# SuperCap-NEW_V2_0.net
KiCad netlist of a schematic drawn in Altium Designer
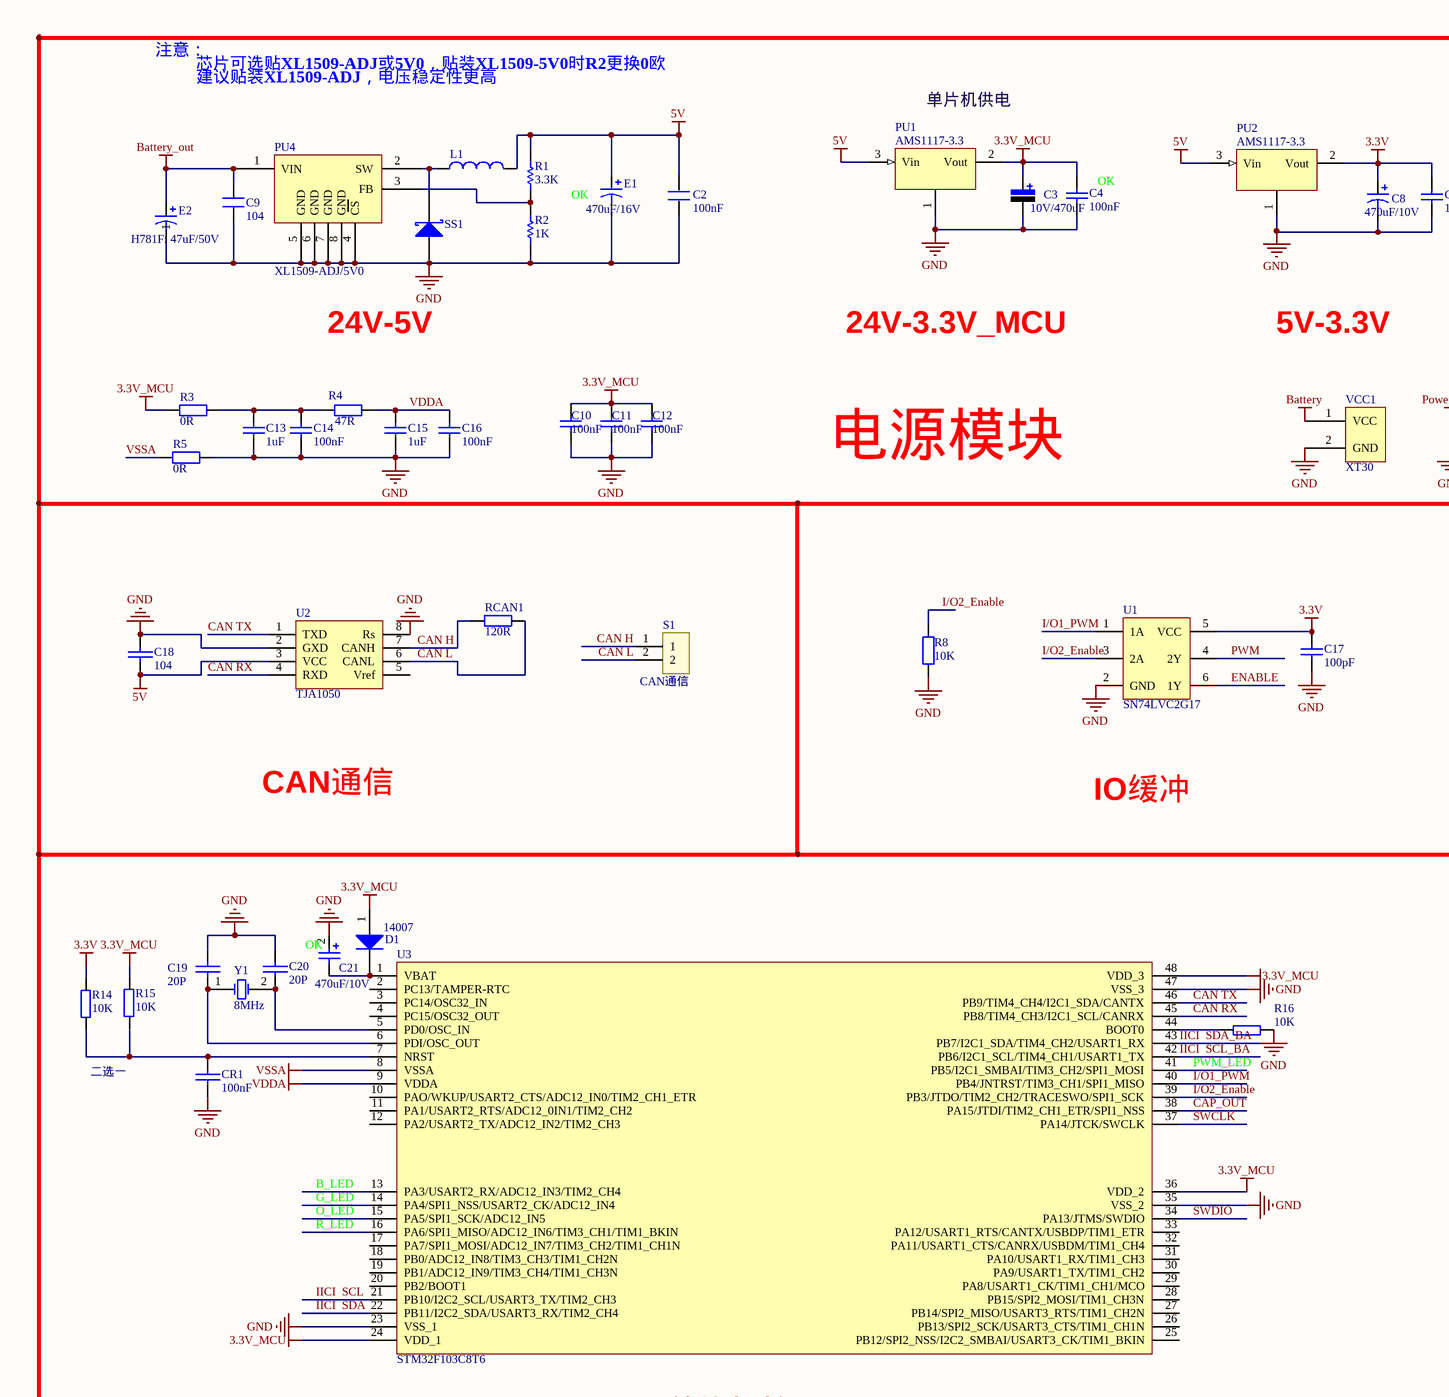
[diagram p0: SuperCap-NEW_V2.0.SchDoc, top left]
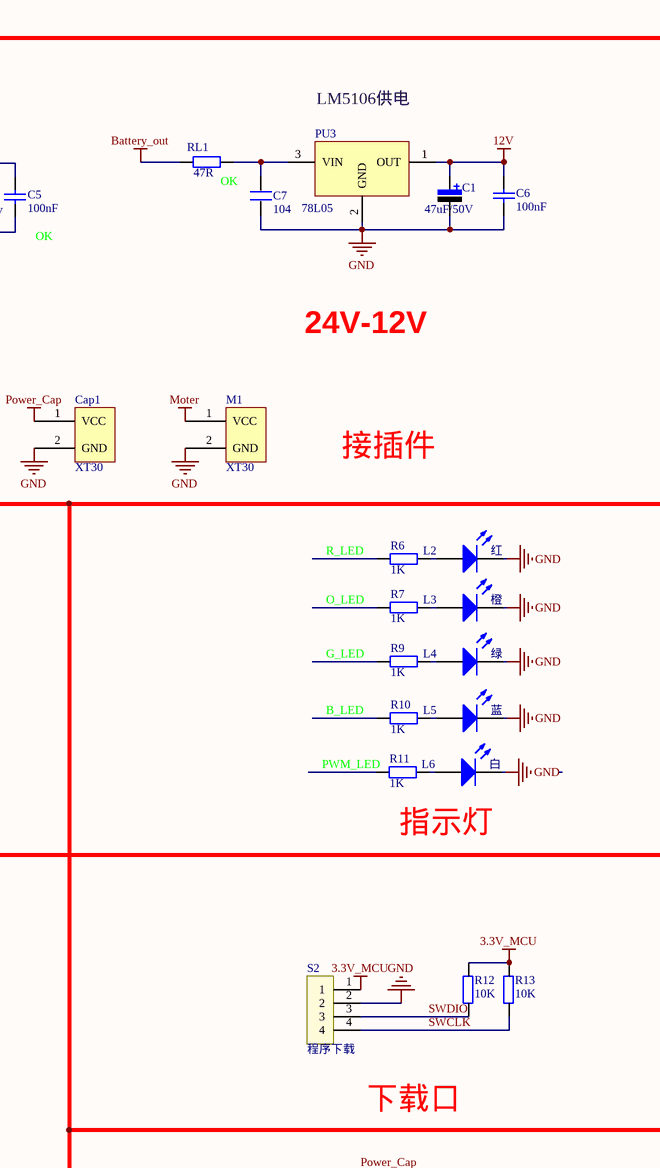
[diagram p1: SuperCap-NEW_V2.0.SchDoc, top right]
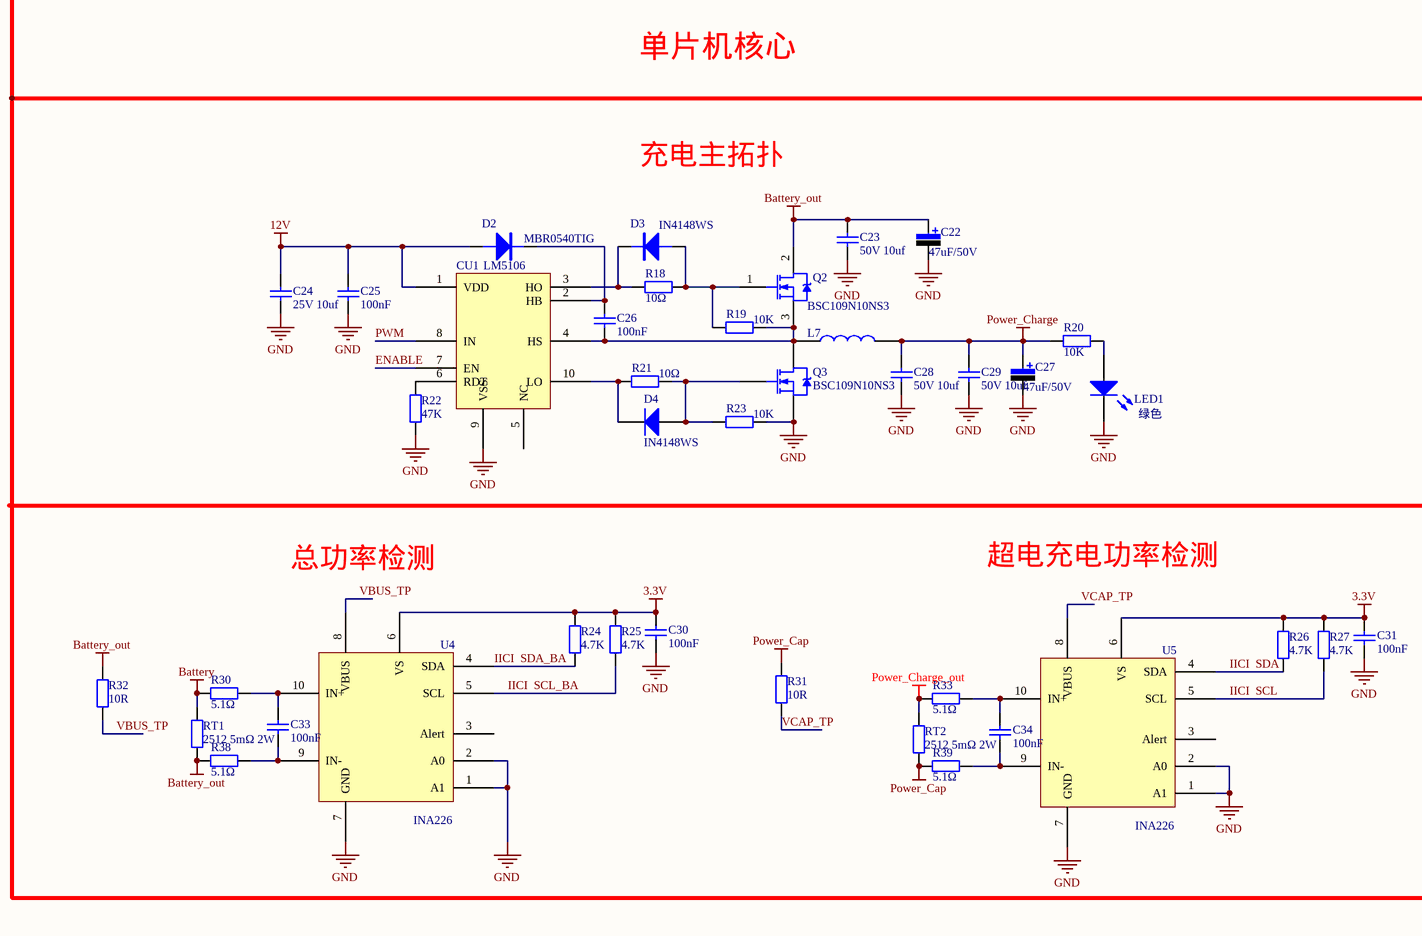
[diagram p2: SuperCap-NEW_V2.0.SchDoc, bottom left]
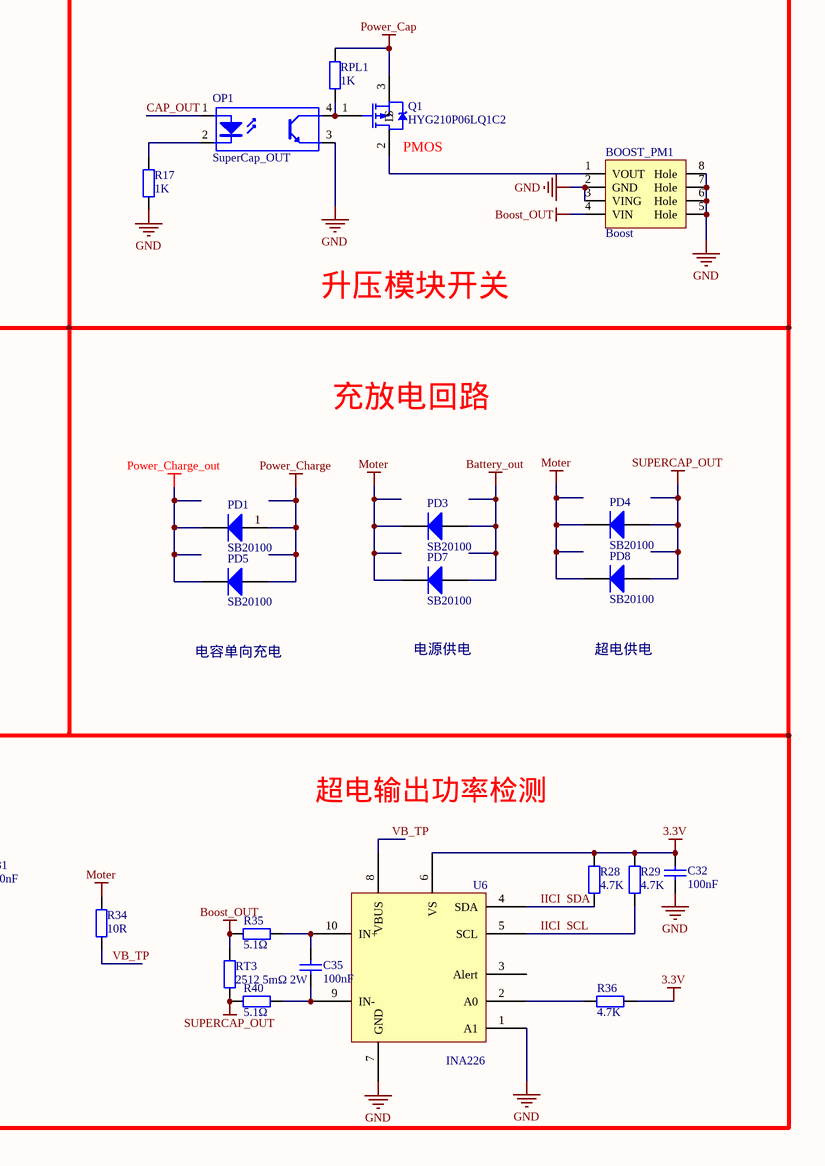
[diagram p3: SuperCap-NEW_V2.0.SchDoc, bottom right]

(export (version "E")
  (design (tool "Eeschema 10.0.6"))
  (components
    (comp (ref "BOOST_PM1")
      (value "Boost")
      (footprint "Boost_Block")
      (libsource (lib "My package") (part "Boost"))
    )
    (comp (ref "C1")
      (value "47uF/50V")
      (footprint "CAP-SMD_BD6.3-L6.6-W6.6-FD")
      (description "极性电解电容")
      (fields (field (name "PUBLISHER") "Altium Limited"))
      (libsource (lib "Fszhang") (part "Cap Pol"))
    )
    (comp (ref "C2") (value "100nF") (footprint "0603C") (libsource (lib "南江主控 原理图库") (part "C")))
    (comp (ref "C3")
      (value "10V/470uF")
      (footprint "CAP-SMD_BD6.3-L6.6-W6.6-FD")
      (description "极性电解电容")
      (fields (field (name "PUBLISHER") "Altium Limited"))
      (libsource (lib "Fszhang") (part "Cap Pol"))
    )
    (comp (ref "C4")
      (value "100nF")
      (footprint "0603C")
      (description "无极性电容")
      (fields (field (name "PUBLISHER") "Altium Limited"))
      (libsource (lib "Fszhang") (part "Cap"))
    )
    (comp (ref "C5")
      (value "100nF")
      (footprint "0603C")
      (description "无极性电容")
      (fields (field (name "PUBLISHER") "Altium Limited"))
      (libsource (lib "Fszhang") (part "Cap"))
    )
    (comp (ref "C6")
      (value "100nF")
      (footprint "0603C")
      (description "无极性电容")
      (fields (field (name "PUBLISHER") "Altium Limited"))
      (libsource (lib "Fszhang") (part "Cap"))
    )
    (comp (ref "C7") (value "104") (footprint "0603C") (libsource (lib "103驱动2") (part "C")))
    (comp (ref "C8")
      (value "470uF/10V")
      (footprint "CAP-SMD_BD6.3-L6.6-W6.6-FD")
      (description "Polarized Capacitor (Radial)")
      (fields (field (name "Comment") "Cap Pol1") (field (name "PUBLISHER") "Altium Limited"))
      (libsource (lib "") (part "Cap Pol1_1"))
    )
    (comp (ref "C9") (value "104") (footprint "0603C") (libsource (lib "南江主控 原理图库") (part "C")))
    (comp (ref "C10")
      (value "100nF")
      (footprint "0603C")
      (description "无极性电容")
      (fields (field (name "PUBLISHER") "Altium Limited"))
      (libsource (lib "Fszhang") (part "Cap"))
    )
    (comp (ref "C11")
      (value "100nF")
      (footprint "0603C")
      (description "无极性电容")
      (fields (field (name "PUBLISHER") "Altium Limited"))
      (libsource (lib "Fszhang") (part "Cap"))
    )
    (comp (ref "C12")
      (value "100nF")
      (footprint "0603C")
      (description "无极性电容")
      (fields (field (name "PUBLISHER") "Altium Limited"))
      (libsource (lib "Fszhang") (part "Cap"))
    )
    (comp (ref "C13")
      (value "1uF")
      (footprint "0603C")
      (description "无极性电容")
      (fields (field (name "PUBLISHER") "Altium Limited"))
      (libsource (lib "Fszhang") (part "Cap"))
    )
    (comp (ref "C14")
      (value "100nF")
      (footprint "0603C")
      (description "无极性电容")
      (fields (field (name "PUBLISHER") "Altium Limited"))
      (libsource (lib "Fszhang") (part "Cap"))
    )
    (comp (ref "C15")
      (value "1uF")
      (footprint "0603C")
      (description "无极性电容")
      (fields (field (name "PUBLISHER") "Altium Limited"))
      (libsource (lib "Fszhang") (part "Cap"))
    )
    (comp (ref "C16")
      (value "100nF")
      (footprint "0603C")
      (description "无极性电容")
      (fields (field (name "PUBLISHER") "Altium Limited"))
      (libsource (lib "Fszhang") (part "Cap"))
    )
    (comp (ref "C17")
      (value "100pF")
      (footprint "0603C")
      (description "Capacitor")
      (fields (field (name "Comment") "Cap") (field (name "PUBLISHER") "Altium Limited"))
      (libsource (lib "Miscellaneous Devices") (part "Cap"))
    )
    (comp (ref "C18") (value "104") (footprint "0603C") (libsource (lib "ZBC124Schlib1") (part "CAP-1")))
    (comp (ref "C19") (value "20P") (footprint "0603C") (libsource (lib "ZBC124Schlib1") (part "CAP-1")))
    (comp (ref "C20") (value "20P") (footprint "0603C") (libsource (lib "ZBC124Schlib1") (part "CAP-1")))
    (comp (ref "C21")
      (value "470uF/10V")
      (footprint "CAP-SMD_BD6.3-L6.6-W6.6-FD")
      (description "Polarized Capacitor (Radial)")
      (fields (field (name "PUBLISHER") "Altium Limited"))
      (libsource (lib "*") (part "Cap Pol1"))
    )
    (comp (ref "C22")
      (value "47uF/50V")
      (footprint "CAP-SMD_BD6.3-L6.6-W6.6-FD")
      (description "极性电解电容")
      (fields (field (name "PUBLISHER") "Altium Limited"))
      (libsource (lib "Fszhang") (part "Cap Pol"))
    )
    (comp (ref "C23")
      (value "50V 10uf")
      (footprint "0603C")
      (description "无极性电容")
      (fields (field (name "PUBLISHER") "Altium Limited"))
      (libsource (lib "Fszhang") (part "Cap"))
    )
    (comp (ref "C24")
      (value "25V 10uf")
      (footprint "0603C")
      (description "无极性电容")
      (fields (field (name "PUBLISHER") "Altium Limited"))
      (libsource (lib "Fszhang") (part "Cap"))
    )
    (comp (ref "C25")
      (value "100nF")
      (footprint "0603C")
      (description "无极性电容")
      (fields (field (name "PUBLISHER") "Altium Limited"))
      (libsource (lib "Fszhang") (part "Cap"))
    )
    (comp (ref "C26")
      (value "100nF")
      (footprint "0603C")
      (description "无极性电容")
      (fields (field (name "PUBLISHER") "Altium Limited"))
      (libsource (lib "Fszhang") (part "Cap"))
    )
    (comp (ref "C27")
      (value "47uF/50V")
      (footprint "CAP-SMD_BD6.3-L6.6-W6.6-FD")
      (description "极性电解电容")
      (fields (field (name "PUBLISHER") "Altium Limited"))
      (libsource (lib "Fszhang") (part "Cap Pol"))
    )
    (comp (ref "C28")
      (value "50V 10uf")
      (footprint "0603C")
      (description "无极性电容")
      (fields (field (name "PUBLISHER") "Altium Limited"))
      (libsource (lib "Fszhang") (part "Cap"))
    )
    (comp (ref "C29")
      (value "50V 10uf")
      (footprint "0603C")
      (description "无极性电容")
      (fields (field (name "PUBLISHER") "Altium Limited"))
      (libsource (lib "Fszhang") (part "Cap"))
    )
    (comp (ref "C30")
      (value "100nF")
      (footprint "0603C")
      (description "无极性电容")
      (fields (field (name "PUBLISHER") "Altium Limited"))
      (libsource (lib "Fszhang") (part "Cap"))
    )
    (comp (ref "C31")
      (value "100nF")
      (footprint "0603C")
      (description "无极性电容")
      (fields (field (name "PUBLISHER") "Altium Limited"))
      (libsource (lib "Fszhang") (part "Cap"))
    )
    (comp (ref "C32")
      (value "100nF")
      (footprint "0603C")
      (description "无极性电容")
      (fields (field (name "PUBLISHER") "Altium Limited"))
      (libsource (lib "Fszhang") (part "Cap"))
    )
    (comp (ref "C33")
      (value "100nF")
      (footprint "0603C")
      (description "无极性电容")
      (fields (field (name "PUBLISHER") "Altium Limited"))
      (libsource (lib "Fszhang") (part "Cap"))
    )
    (comp (ref "C34")
      (value "100nF")
      (footprint "0603C")
      (description "无极性电容")
      (fields (field (name "PUBLISHER") "Altium Limited"))
      (libsource (lib "Fszhang") (part "Cap"))
    )
    (comp (ref "C35")
      (value "100nF")
      (footprint "0603C")
      (description "无极性电容")
      (fields (field (name "PUBLISHER") "Altium Limited"))
      (libsource (lib "Fszhang") (part "Cap"))
    )
    (comp (ref "Cap1") (value "XT30") (footprint "XT30") (libsource (lib "电源模块") (part "JP-2")))
    (comp (ref "CR1") (value "100nF") (footprint "0603C") (libsource (lib "ZBC124Schlib1") (part "CAP-1")))
    (comp (ref "CU1") (value "LM5106") (footprint "MSOP_10") (libsource (lib "Schlib3") (part "Component_1")))
    (comp (ref "D1")
      (value "14007")
      (footprint "SOD123")
      (description "High Conductance Fast Diode")
      (fields (field (name "PUBLISHER") "Altium Limited"))
      (libsource (lib "") (part "Diode 1N914_1"))
    )
    (comp (ref "D2") (value "MBR0540TIG") (footprint "SOD123") (libsource (lib "ZBC124Schlib1") (part "D-1")))
    (comp (ref "D3") (value "IN4148WS") (footprint "SOD123") (libsource (lib "ZBC124Schlib1") (part "D-1")))
    (comp (ref "D4")
      (value "IN4148WS")
      (footprint "SOD123")
      (description "High Conductance Fast Diode")
      (fields (field (name "PUBLISHER") "Altium Limited"))
      (libsource (lib "Miscellaneous Devices") (part "Diode 1N914"))
    )
    (comp (ref "E1")
      (value "470uF/16V")
      (footprint "CAP-SMD_BD8.0-L8.3-W8.3-FD")
      (description "Polarized Capacitor (Radial)")
      (fields (field (name "Comment") "Cap Pol1") (field (name "PUBLISHER") "Altium Limited"))
      (libsource (lib "") (part "Cap Pol1_1"))
    )
    (comp (ref "E2")
      (value "Cap Pol1")
      (footprint "CAP-SMD_BD8.0-L8.3-W8.3-FD")
      (description "Polarized Capacitor (Radial)")
      (fields (field (name "H781F") "47uF/50V") (field (name "PUBLISHER") "Altium Limited"))
      (libsource (lib "Miscellaneous Devices") (part "Cap Pol1"))
    )
    (comp (ref "L1")
      (value "Inductor")
      (footprint "L 6*6")
      (fields (field (name "PUBLISHER") "Altium Limited"))
      (libsource (lib "Miscellaneous Devices") (part "Inductor"))
    )
    (comp (ref "L2")
      (value "红")
      (footprint "LED_0805")
      (description "发光二极管")
      (fields (field (name "PUBLISHER") "Altium Limited"))
      (libsource (lib "Fszhang") (part "LED0"))
    )
    (comp (ref "L3")
      (value "橙")
      (footprint "LED_0805")
      (description "发光二极管")
      (fields (field (name "PUBLISHER") "Altium Limited"))
      (libsource (lib "Fszhang") (part "LED0"))
    )
    (comp (ref "L4")
      (value "绿")
      (footprint "LED_0805")
      (description "发光二极管")
      (fields (field (name "PUBLISHER") "Altium Limited"))
      (libsource (lib "Fszhang") (part "LED0"))
    )
    (comp (ref "L5")
      (value "蓝")
      (footprint "LED_0805")
      (description "发光二极管")
      (fields (field (name "PUBLISHER") "Altium Limited"))
      (libsource (lib "Fszhang") (part "LED0"))
    )
    (comp (ref "L6")
      (value "白")
      (footprint "LED_0805")
      (description "发光二极管")
      (fields (field (name "PUBLISHER") "Altium Limited"))
      (libsource (lib "Fszhang") (part "LED0"))
    )
    (comp (ref "L7")
      (value "68UH")
      (footprint "IND-TH_L14.0-W6.5-P8.00-D0.6")
      (libsource (lib "103驱动2") (part "Inductance"))
    )
    (comp (ref "LED1")
      (value "绿色")
      (footprint "LED_0805")
      (description "发光二极管")
      (fields (field (name "PUBLISHER") "Altium Limited"))
      (libsource (lib "Fszhang") (part "LED0"))
    )
    (comp (ref "M1") (value "XT30") (footprint "XT30") (libsource (lib "电源模块") (part "JP-2")))
    (comp (ref "OP1")
      (value "SuperCap_OUT")
      (footprint "SOP-4_L6.5-W4.6-P2.54-LS10.2-TL")
      (description "4-Pin Phototransistor Optocoupler")
      (fields (field (name "PUBLISHER") "Altium Limited"))
      (libsource (lib "Miscellaneous Devices") (part "Optoisolator1"))
    )
    (comp (ref "PD1")
      (value "SB20100")
      (footprint "TO-277_3P-L5.4-W4.0-LS6.5-TR")
      (description "High Conductance Fast Diode")
      (fields (field (name "PUBLISHER") "Altium Limited"))
      (libsource (lib "") (part "Diode 1N914_1"))
    )
    (comp (ref "PD3")
      (value "SB20100")
      (footprint "TO-277_3P-L5.4-W4.0-LS6.5-TR")
      (description "High Conductance Fast Diode")
      (fields (field (name "PUBLISHER") "Altium Limited"))
      (libsource (lib "Miscellaneous Devices") (part "Diode 1N914"))
    )
    (comp (ref "PD4")
      (value "SB20100")
      (footprint "TO-277_3P-L5.4-W4.0-LS6.5-TR")
      (description "High Conductance Fast Diode")
      (fields (field (name "PUBLISHER") "Altium Limited"))
      (libsource (lib "Miscellaneous Devices") (part "Diode 1N914"))
    )
    (comp (ref "PD5")
      (value "SB20100")
      (footprint "TO-277_3P-L5.4-W4.0-LS6.5-TR")
      (description "High Conductance Fast Diode")
      (fields (field (name "PUBLISHER") "Altium Limited"))
      (libsource (lib "Miscellaneous Devices") (part "Diode 1N914"))
    )
    (comp (ref "PD7")
      (value "SB20100")
      (footprint "TO-277_3P-L5.4-W4.0-LS6.5-TR")
      (description "High Conductance Fast Diode")
      (fields (field (name "PUBLISHER") "Altium Limited"))
      (libsource (lib "Miscellaneous Devices") (part "Diode 1N914"))
    )
    (comp (ref "PD8")
      (value "SB20100")
      (footprint "TO-277_3P-L5.4-W4.0-LS6.5-TR")
      (description "High Conductance Fast Diode")
      (fields (field (name "PUBLISHER") "Altium Limited"))
      (libsource (lib "Miscellaneous Devices") (part "Diode 1N914"))
    )
    (comp (ref "PU1") (value "AMS1117-3.3") (footprint "SOT-223") (libsource (lib "*") (part "LD1117")))
    (comp (ref "PU2") (value "AMS1117-3.3") (footprint "SOT-223") (libsource (lib "*") (part "LD1117")))
    (comp (ref "PU3")
      (value "78L05")
      (footprint "SOT-89-3_L4.5-W2.5-P1.50-LS4.2-BR")
      (libsource (lib "My package") (part "78L05"))
    )
    (comp (ref "PU4")
      (value "XL1509-ADJ/5V0")
      (footprint "SOP8 N")
      (libsource (lib "电源转接板") (part "XL1509-ADJ"))
    )
    (comp (ref "Q1")
      (value "HYG210P06LQ1C2")
      (footprint "MOS_PQFN")
      (description "P-Channel Power MOSFET")
      (fields (field (name "PUBLISHER") "Altium Limited"))
      (libsource (lib "Miscellaneous Devices") (part "PMOS-2"))
    )
    (comp (ref "Q2")
      (value "BSC109N10NS3")
      (footprint "PDFN-8_L4.9-W5.8-P1.27-LS6.1-BL_2")
      (description "N-Channel Power MOSFET")
      (fields (field (name "PUBLISHER") "Altium Limited"))
      (libsource (lib "Miscellaneous Devices") (part "NMOS-2"))
    )
    (comp (ref "Q3")
      (value "BSC109N10NS3")
      (footprint "PDFN-8_L4.9-W5.8-P1.27-LS6.1-BL_2")
      (description "N-Channel Power MOSFET")
      (fields (field (name "PUBLISHER") "Altium Limited"))
      (libsource (lib "") (part "NMOS-2_1"))
    )
    (comp (ref "R1")
      (value "3.3K")
      (footprint "R0603")
      (description "Resistor")
      (fields (field (name "Comment") "Res1") (field (name "PUBLISHER") "Altium Limited"))
      (libsource (lib "Miscellaneous Devices") (part "Res1"))
    )
    (comp (ref "R2")
      (value "1K")
      (footprint "R0603")
      (description "Resistor")
      (fields (field (name "Comment") "Res1") (field (name "PUBLISHER") "Altium Limited"))
      (libsource (lib "Miscellaneous Devices") (part "Res1"))
    )
    (comp (ref "R3")
      (value "0R")
      (footprint "0603-1")
      (description "贴片电阻")
      (fields (field (name "PUBLISHER") "Altium Limited"))
      (libsource (lib "") (part "Res1_2"))
    )
    (comp (ref "R4")
      (value "47R")
      (footprint "0603-1")
      (description "贴片电阻")
      (fields (field (name "PUBLISHER") "Altium Limited"))
      (libsource (lib "") (part "Res1_2"))
    )
    (comp (ref "R5")
      (value "0R")
      (footprint "0603-1")
      (description "贴片电阻")
      (fields (field (name "PUBLISHER") "Altium Limited"))
      (libsource (lib "") (part "Res1_2"))
    )
    (comp (ref "R6")
      (value "1K")
      (footprint "0603-1")
      (description "Resistor")
      (fields (field (name "Comment") "Res2") (field (name "PUBLISHER") "Altium Limited"))
      (libsource (lib "") (part "Res2_1"))
    )
    (comp (ref "R7")
      (value "1K")
      (footprint "0603-1")
      (description "Resistor")
      (fields (field (name "Comment") "Res2") (field (name "PUBLISHER") "Altium Limited"))
      (libsource (lib "Miscellaneous Devices") (part "Res2"))
    )
    (comp (ref "R8")
      (value "10K")
      (footprint "0603-1")
      (description "Resistor")
      (fields (field (name "Comment") "Res2") (field (name "PUBLISHER") "Altium Limited"))
      (libsource (lib "") (part "Res2_2"))
    )
    (comp (ref "R9")
      (value "1K")
      (footprint "0603-1")
      (description "Resistor")
      (fields (field (name "Comment") "Res2") (field (name "PUBLISHER") "Altium Limited"))
      (libsource (lib "Miscellaneous Devices") (part "Res2"))
    )
    (comp (ref "R10")
      (value "1K")
      (footprint "0603-1")
      (description "Resistor")
      (fields (field (name "Comment") "Res2") (field (name "PUBLISHER") "Altium Limited"))
      (libsource (lib "Miscellaneous Devices") (part "Res2"))
    )
    (comp (ref "R11")
      (value "1K")
      (footprint "0603-1")
      (description "Resistor")
      (fields (field (name "Comment") "Res2") (field (name "PUBLISHER") "Altium Limited"))
      (libsource (lib "Miscellaneous Devices") (part "Res2"))
    )
    (comp (ref "R12") (value "10K") (footprint "0603-1") (libsource (lib "WARSHIP") (part "R")))
    (comp (ref "R13") (value "10K") (footprint "0603-1") (libsource (lib "WARSHIP") (part "R")))
    (comp (ref "R14") (value "10K") (footprint "0603-1") (libsource (lib "WARSHIP") (part "R")))
    (comp (ref "R15") (value "10K") (footprint "0603-1") (libsource (lib "WARSHIP") (part "R")))
    (comp (ref "R16") (value "10K") (footprint "0603-1") (libsource (lib "WARSHIP") (part "R")))
    (comp (ref "R17")
      (value "1K")
      (footprint "0603-1")
      (description "贴片电阻")
      (fields (field (name "PUBLISHER") "Altium Limited"))
      (libsource (lib "Fszhang") (part "Res1"))
    )
    (comp (ref "R18")
      (value "10Ω")
      (footprint "0603-1")
      (description "贴片电阻")
      (fields (field (name "PUBLISHER") "Altium Limited"))
      (libsource (lib "") (part "Res1_2"))
    )
    (comp (ref "R19")
      (value "10K")
      (footprint "0603-1")
      (description "贴片电阻")
      (fields (field (name "PUBLISHER") "Altium Limited"))
      (libsource (lib "") (part "Res1_2"))
    )
    (comp (ref "R20")
      (value "10K")
      (footprint "0603-1")
      (description "贴片电阻")
      (fields (field (name "PUBLISHER") "Altium Limited"))
      (libsource (lib "") (part "Res1_1"))
    )
    (comp (ref "R21")
      (value "10Ω")
      (footprint "0603-1")
      (description "贴片电阻")
      (fields (field (name "PUBLISHER") "Altium Limited"))
      (libsource (lib "") (part "Res1_2"))
    )
    (comp (ref "R22")
      (value "47K")
      (footprint "0603-1")
      (description "贴片电阻")
      (fields (field (name "PUBLISHER") "Altium Limited"))
      (libsource (lib "Fszhang") (part "Res1"))
    )
    (comp (ref "R23")
      (value "10K")
      (footprint "0603-1")
      (description "贴片电阻")
      (fields (field (name "PUBLISHER") "Altium Limited"))
      (libsource (lib "") (part "Res1_2"))
    )
    (comp (ref "R24")
      (value "4.7K")
      (footprint "0603-1")
      (description "贴片电阻")
      (fields (field (name "PUBLISHER") "Altium Limited"))
      (libsource (lib "Fszhang") (part "Res1"))
    )
    (comp (ref "R25")
      (value "4.7K")
      (footprint "0603-1")
      (description "贴片电阻")
      (fields (field (name "PUBLISHER") "Altium Limited"))
      (libsource (lib "Fszhang") (part "Res1"))
    )
    (comp (ref "R26")
      (value "4.7K")
      (footprint "0603-1")
      (description "贴片电阻")
      (fields (field (name "PUBLISHER") "Altium Limited"))
      (libsource (lib "Fszhang") (part "Res1"))
    )
    (comp (ref "R27")
      (value "4.7K")
      (footprint "0603-1")
      (description "贴片电阻")
      (fields (field (name "PUBLISHER") "Altium Limited"))
      (libsource (lib "Fszhang") (part "Res1"))
    )
    (comp (ref "R28")
      (value "4.7K")
      (footprint "0603-1")
      (description "贴片电阻")
      (fields (field (name "PUBLISHER") "Altium Limited"))
      (libsource (lib "Fszhang") (part "Res1"))
    )
    (comp (ref "R29")
      (value "4.7K")
      (footprint "0603-1")
      (description "贴片电阻")
      (fields (field (name "PUBLISHER") "Altium Limited"))
      (libsource (lib "Fszhang") (part "Res1"))
    )
    (comp (ref "R30")
      (value "5.1Ω")
      (footprint "0603-1")
      (description "贴片电阻")
      (fields (field (name "PUBLISHER") "Altium Limited"))
      (libsource (lib "") (part "Res1_1"))
    )
    (comp (ref "R31")
      (value "10R")
      (footprint "0603-1")
      (description "Resistor")
      (fields (field (name "Comment") "Res2") (field (name "PUBLISHER") "Altium Limited"))
      (libsource (lib "") (part "Res2_2"))
    )
    (comp (ref "R32")
      (value "10R")
      (footprint "0603-1")
      (description "Resistor")
      (fields (field (name "Comment") "Res2") (field (name "PUBLISHER") "Altium Limited"))
      (libsource (lib "") (part "Res2_2"))
    )
    (comp (ref "R33")
      (value "5.1Ω")
      (footprint "0603-1")
      (description "贴片电阻")
      (fields (field (name "PUBLISHER") "Altium Limited"))
      (libsource (lib "") (part "Res1_1"))
    )
    (comp (ref "R34")
      (value "10R")
      (footprint "0603-1")
      (description "Resistor")
      (fields (field (name "Comment") "Res2") (field (name "PUBLISHER") "Altium Limited"))
      (libsource (lib "") (part "Res2_2"))
    )
    (comp (ref "R35")
      (value "5.1Ω")
      (footprint "0603-1")
      (description "贴片电阻")
      (fields (field (name "PUBLISHER") "Altium Limited"))
      (libsource (lib "") (part "Res1_1"))
    )
    (comp (ref "R36")
      (value "4.7K")
      (footprint "0603-1")
      (description "Resistor")
      (fields (field (name "Comment") "Res2") (field (name "PUBLISHER") "Altium Limited"))
      (libsource (lib "") (part "Res2_1"))
    )
    (comp (ref "R38")
      (value "5.1Ω")
      (footprint "0603-1")
      (description "贴片电阻")
      (fields (field (name "PUBLISHER") "Altium Limited"))
      (libsource (lib "") (part "Res1_1"))
    )
    (comp (ref "R39")
      (value "5.1Ω")
      (footprint "0603-1")
      (description "贴片电阻")
      (fields (field (name "PUBLISHER") "Altium Limited"))
      (libsource (lib "") (part "Res1_1"))
    )
    (comp (ref "R40")
      (value "5.1Ω")
      (footprint "0603-1")
      (description "贴片电阻")
      (fields (field (name "PUBLISHER") "Altium Limited"))
      (libsource (lib "") (part "Res1_1"))
    )
    (comp (ref "RCAN1")
      (value "120R")
      (footprint "0603-1")
      (description "Resistor")
      (fields (field (name "Comment") "Res2") (field (name "PUBLISHER") "Altium Limited"))
      (libsource (lib "") (part "Res2_1"))
    )
    (comp (ref "RL1")
      (value "47R")
      (footprint "0603-1")
      (description "贴片电阻")
      (fields (field (name "PUBLISHER") "Altium Limited"))
      (libsource (lib "") (part "Res1_2"))
    )
    (comp (ref "RPL1")
      (value "1K")
      (footprint "0603-1")
      (description "贴片电阻")
      (fields (field (name "PUBLISHER") "Altium Limited"))
      (libsource (lib "Fszhang") (part "Res1"))
    )
    (comp (ref "RT1")
      (value "2512 5mΩ 2W")
      (footprint "FUSE-SMD_L6.1-W2.7 - duplicate")
      (description "贴片电阻")
      (fields (field (name "PUBLISHER") "Altium Limited"))
      (libsource (lib "Fszhang") (part "Res1"))
    )
    (comp (ref "RT2")
      (value "2512 5mΩ 2W")
      (footprint "FUSE-SMD_L6.1-W2.7 - duplicate")
      (description "贴片电阻")
      (fields (field (name "PUBLISHER") "Altium Limited"))
      (libsource (lib "Fszhang") (part "Res1"))
    )
    (comp (ref "RT3")
      (value "2512 5mΩ 2W")
      (footprint "FUSE-SMD_L6.1-W2.7 - duplicate")
      (description "贴片电阻")
      (fields (field (name "PUBLISHER") "Altium Limited"))
      (libsource (lib "Fszhang") (part "Res1"))
    )
    (comp (ref "S1") (value "CAN通信") (footprint "1.25_2Pin") (libsource (lib "ZBC123Schlib1") (part "S-2")))
    (comp (ref "S2") (value "程序下载") (footprint "S-4") (libsource (lib "ZBC123Schlib1") (part "S-4")))
    (comp (ref "SS1")
      (value "D Schottky")
      (footprint "贴片M7")
      (description "Schottky Diode")
      (fields (field (name "PUBLISHER") "Altium Limited"))
      (libsource (lib "Miscellaneous Devices") (part "D Schottky"))
    )
    (comp (ref "U1")
      (value "SN74LVC2G17")
      (footprint "SC-70-6_L2.0-W1.3-P0.65-LS2.1-BL")
      (libsource (lib "My package") (part "SN74LVC2G17"))
    )
    (comp (ref "U2") (value "TJA1050") (footprint "SOP8 N") (libsource (lib "底盘主控") (part "24C02")))
    (comp (ref "U3")
      (value "STM32F103C8T6")
      (footprint "LQFP-48_M")
      (libsource (lib "WARSHIP") (part "STM32F103C8T6"))
    )
    (comp (ref "U4") (value "INA226") (footprint "MSOP_10") (libsource (lib "Schlib4") (part "Component_1")))
    (comp (ref "U5") (value "INA226") (footprint "MSOP_10") (libsource (lib "Schlib4") (part "Component_1")))
    (comp (ref "U6") (value "INA226") (footprint "MSOP_10") (libsource (lib "Schlib4") (part "Component_1")))
    (comp (ref "VCC1") (value "XT30") (footprint "XT30") (libsource (lib "电源模块") (part "JP-2")))
    (comp (ref "Y1")
      (value "8MHz")
      (footprint "X-SM49")
      (description "Crystal Oscillator")
      (fields (field (name "PUBLISHER") "Altium Limited"))
      (libsource (lib "WARSHIP") (part "XTAL"))
    )
  )
  (nets
    (net (code "2") (name "/B_LED") (class "Default")
      (node (ref "R10") (pin "2") (pinfunction "2_2") (pintype "passive"))
      (node (ref "U3") (pin "13") (pinfunction "PA3/USART2_RX/ADC12_IN3/TIM2_CH4_13") (pintype "passive"))
    )
    (net (code "3") (name "/CAN H") (class "Default")
      (node (ref "RCAN1") (pin "1") (pinfunction "1_1") (pintype "passive"))
      (node (ref "S1") (pin "1") (pinfunction "1_1") (pintype "passive"))
      (node (ref "U2") (pin "7") (pinfunction "CANH_7") (pintype "passive"))
    )
    (net (code "4") (name "/CAN L") (class "Default")
      (node (ref "RCAN1") (pin "2") (pinfunction "2_2") (pintype "passive"))
      (node (ref "S1") (pin "2") (pinfunction "2_2") (pintype "passive"))
      (node (ref "U2") (pin "6") (pinfunction "CANL_6") (pintype "passive"))
    )
    (net (code "5") (name "/CAN RX") (class "Default")
      (node (ref "U2") (pin "4") (pinfunction "RXD_4") (pintype "passive"))
      (node (ref "U3") (pin "45") (pinfunction "PB8/TIM4_CH3/I2C1_SCL/CANRX_45") (pintype "passive"))
    )
    (net (code "6") (name "/CAN TX") (class "Default")
      (node (ref "U2") (pin "1") (pinfunction "TXD_1") (pintype "passive"))
      (node (ref "U3") (pin "46") (pinfunction "PB9/TIM4_CH4/I2C1_SDA/CANTX_46") (pintype "passive"))
    )
    (net (code "7") (name "/CAP_OUT") (class "Default")
      (node (ref "OP1") (pin "1") (pinfunction "A_1") (pintype "passive"))
      (node (ref "U3") (pin "38") (pinfunction "PA15/JTDI/TIM2_CH1_ETR/SPI1_NSS_38") (pintype "passive"))
    )
    (net (code "8") (name "/ENABLE") (class "Default")
      (node (ref "CU1") (pin "7") (pinfunction "EN_7") (pintype "passive"))
      (node (ref "U1") (pin "6") (pinfunction "1Y_6") (pintype "passive"))
    )
    (net (code "9") (name "/G_LED") (class "Default")
      (node (ref "R9") (pin "2") (pinfunction "2_2") (pintype "passive"))
      (node (ref "U3") (pin "14") (pinfunction "PA4/SPI1_NSS/USART2_CK/ADC12_IN4_14") (pintype "passive"))
    )
    (net (code "10") (name "/IICI  SCL") (class "Default")
      (node (ref "R27") (pin "2") (pinfunction "2_2") (pintype "passive"))
      (node (ref "R29") (pin "2") (pinfunction "2_2") (pintype "passive"))
      (node (ref "U3") (pin "21") (pinfunction "PB10/I2C2_SCL/USART3_TX/TIM2_CH3_21") (pintype "passive"))
      (node (ref "U5") (pin "5") (pinfunction "SCL_5") (pintype "passive"))
      (node (ref "U6") (pin "5") (pinfunction "SCL_5") (pintype "passive"))
    )
    (net (code "11") (name "/IICI  SCL_BA") (class "Default")
      (node (ref "R25") (pin "2") (pinfunction "2_2") (pintype "passive"))
      (node (ref "U3") (pin "42") (pinfunction "PB6/I2C1_SCL/TIM4_CH1/USART1_TX_42") (pintype "passive"))
      (node (ref "U4") (pin "5") (pinfunction "SCL_5") (pintype "passive"))
    )
    (net (code "12") (name "/IICI  SDA") (class "Default")
      (node (ref "R26") (pin "2") (pinfunction "2_2") (pintype "passive"))
      (node (ref "R28") (pin "2") (pinfunction "2_2") (pintype "passive"))
      (node (ref "U3") (pin "22") (pinfunction "PB11/I2C2_SDA/USART3_RX/TIM2_CH4_22") (pintype "passive"))
      (node (ref "U5") (pin "4") (pinfunction "SDA_4") (pintype "passive"))
      (node (ref "U6") (pin "4") (pinfunction "SDA_4") (pintype "passive"))
    )
    (net (code "13") (name "/IICI  SDA_BA") (class "Default")
      (node (ref "R24") (pin "2") (pinfunction "2_2") (pintype "passive"))
      (node (ref "U3") (pin "43") (pinfunction "PB7/I2C1_SDA/TIM4_CH2/USART1_RX_43") (pintype "passive"))
      (node (ref "U4") (pin "4") (pinfunction "SDA_4") (pintype "passive"))
    )
    (net (code "14") (name "/I{slash}O1_PWM") (class "Default")
      (node (ref "U1") (pin "1") (pinfunction "1A_1") (pintype "passive"))
      (node (ref "U3") (pin "40") (pinfunction "PB4/JNTRST/TIM3_CH1/SPI1_MISO_40") (pintype "passive"))
    )
    (net (code "15") (name "/I{slash}O2_Enable") (class "Default")
      (node (ref "R8") (pin "1") (pinfunction "1_1") (pintype "passive"))
      (node (ref "U1") (pin "3") (pinfunction "2A_3") (pintype "passive"))
      (node (ref "U3") (pin "39") (pinfunction "PB3/JTDO/TIM2_CH2/TRACESWO/SPI1_SCK_39") (pintype "passive"))
    )
    (net (code "17") (name "/O_LED") (class "Default")
      (node (ref "R7") (pin "2") (pinfunction "2_2") (pintype "passive"))
      (node (ref "U3") (pin "15") (pinfunction "PA5/SPI1_SCK/ADC12_IN5_15") (pintype "passive"))
    )
    (net (code "18") (name "/PWM") (class "Default")
      (node (ref "CU1") (pin "8") (pinfunction "IN_8") (pintype "passive"))
      (node (ref "U1") (pin "4") (pinfunction "2Y_4") (pintype "passive"))
    )
    (net (code "19") (name "/PWM_LED") (class "Default")
      (node (ref "R11") (pin "2") (pinfunction "2_2") (pintype "passive"))
      (node (ref "U3") (pin "41") (pinfunction "PB5/I2C1_SMBAI/TIM3_CH2/SPI1_MOSI_41") (pintype "passive"))
    )
    (net (code "20") (name "/R_LED") (class "Default")
      (node (ref "R6") (pin "1") (pinfunction "1_1") (pintype "passive"))
      (node (ref "U3") (pin "16") (pinfunction "PA6/SPI1_MISO/ADC12_IN6/TIM3_CH1/TIM1_BKIN_16") (pintype "passive"))
    )
    (net (code "21") (name "/SWCLK") (class "Default")
      (node (ref "R13") (pin "2") (pintype "passive"))
      (node (ref "S2") (pin "4") (pinfunction "4_4") (pintype "passive"))
      (node (ref "U3") (pin "37") (pinfunction "PA14/JTCK/SWCLK_37") (pintype "passive"))
    )
    (net (code "22") (name "/SWDIO") (class "Default")
      (node (ref "R12") (pin "2") (pintype "passive"))
      (node (ref "S2") (pin "3") (pinfunction "3_3") (pintype "passive"))
      (node (ref "U3") (pin "34") (pinfunction "PA13/JTMS/SWDIO_34") (pintype "passive"))
    )
    (net (code "23") (name "/VBUS_TP") (class "Default")
      (node (ref "R32") (pin "2") (pinfunction "2_2") (pintype "passive"))
      (node (ref "U4") (pin "8") (pinfunction "VBUS_8") (pintype "passive"))
    )
    (net (code "24") (name "/VB_TP") (class "Default")
      (node (ref "R34") (pin "2") (pinfunction "2_2") (pintype "passive"))
      (node (ref "U6") (pin "8") (pinfunction "VBUS_8") (pintype "passive"))
    )
    (net (code "25") (name "/VCAP_TP") (class "Default")
      (node (ref "R31") (pin "2") (pinfunction "2_2") (pintype "passive"))
      (node (ref "U5") (pin "8") (pinfunction "VBUS_8") (pintype "passive"))
    )
    (net (code "27") (name "3.3V") (class "Default")
      (node (ref "C17") (pin "2") (pinfunction "2_2") (pintype "passive"))
      (node (ref "C30") (pin "1") (pinfunction "1_1") (pintype "passive"))
      (node (ref "C31") (pin "1") (pinfunction "1_1") (pintype "passive"))
      (node (ref "C32") (pin "1") (pinfunction "1_1") (pintype "passive"))
      (node (ref "C5") (pin "1") (pinfunction "1_1") (pintype "passive"))
      (node (ref "C8") (pin "1") (pinfunction "1_1") (pintype "passive"))
      (node (ref "PU2") (pin "2") (pinfunction "Vout_2") (pintype "power_in"))
      (node (ref "R14") (pin "1") (pintype "passive"))
      (node (ref "R24") (pin "1") (pinfunction "1_1") (pintype "passive"))
      (node (ref "R25") (pin "1") (pinfunction "1_1") (pintype "passive"))
      (node (ref "R26") (pin "1") (pinfunction "1_1") (pintype "passive"))
      (node (ref "R27") (pin "1") (pinfunction "1_1") (pintype "passive"))
      (node (ref "R28") (pin "1") (pinfunction "1_1") (pintype "passive"))
      (node (ref "R29") (pin "1") (pinfunction "1_1") (pintype "passive"))
      (node (ref "R36") (pin "2") (pinfunction "2_2") (pintype "passive"))
      (node (ref "U1") (pin "5") (pinfunction "VCC_5") (pintype "passive"))
      (node (ref "U4") (pin "6") (pinfunction "VS_6") (pintype "passive"))
      (node (ref "U5") (pin "6") (pinfunction "VS_6") (pintype "passive"))
      (node (ref "U6") (pin "6") (pinfunction "VS_6") (pintype "passive"))
    )
    (net (code "28") (name "3.3V_MCU") (class "Default")
      (node (ref "C10") (pin "1") (pinfunction "1_1") (pintype "passive"))
      (node (ref "C11") (pin "1") (pinfunction "1_1") (pintype "passive"))
      (node (ref "C12") (pin "1") (pinfunction "1_1") (pintype "passive"))
      (node (ref "C3") (pin "1") (pinfunction "1_1") (pintype "passive"))
      (node (ref "C4") (pin "1") (pinfunction "1_1") (pintype "passive"))
      (node (ref "D1") (pin "1") (pinfunction "A_1") (pintype "passive"))
      (node (ref "PU1") (pin "2") (pinfunction "Vout_2") (pintype "power_in"))
      (node (ref "R12") (pin "1") (pintype "passive"))
      (node (ref "R13") (pin "1") (pintype "passive"))
      (node (ref "R15") (pin "1") (pintype "passive"))
      (node (ref "R3") (pin "1") (pinfunction "1_1") (pintype "passive"))
      (node (ref "S2") (pin "1") (pinfunction "1_1") (pintype "passive"))
      (node (ref "U3") (pin "24") (pinfunction "VDD_1_24") (pintype "passive"))
      (node (ref "U3") (pin "36") (pinfunction "VDD_2_36") (pintype "passive"))
      (node (ref "U3") (pin "48") (pinfunction "VDD_3_48") (pintype "passive"))
    )
    (net (code "29") (name "5V") (class "Default")
      (node (ref "C18") (pin "2") (pinfunction "2_2") (pintype "passive"))
      (node (ref "C2") (pin "2") (pintype "passive"))
      (node (ref "E1") (pin "1") (pinfunction "1_1") (pintype "passive"))
      (node (ref "L1") (pin "2") (pinfunction "2_2") (pintype "passive"))
      (node (ref "PU1") (pin "3") (pinfunction "Vin_3") (pintype "input"))
      (node (ref "PU2") (pin "3") (pinfunction "Vin_3") (pintype "input"))
      (node (ref "R1") (pin "2") (pinfunction "2_2") (pintype "passive"))
      (node (ref "U2") (pin "3") (pinfunction "VCC_3") (pintype "passive"))
    )
    (net (code "30") (name "12V") (class "Default")
      (node (ref "C1") (pin "1") (pinfunction "1_1") (pintype "passive"))
      (node (ref "C24") (pin "1") (pinfunction "1_1") (pintype "passive"))
      (node (ref "C25") (pin "1") (pinfunction "1_1") (pintype "passive"))
      (node (ref "C6") (pin "1") (pinfunction "1_1") (pintype "passive"))
      (node (ref "CU1") (pin "1") (pinfunction "VDD_1") (pintype "passive"))
      (node (ref "D2") (pin "1") (pinfunction "1_1") (pintype "passive"))
      (node (ref "PU3") (pin "1") (pinfunction "OUT_1") (pintype "passive"))
    )
    (net (code "31") (name "Battery") (class "Default")
      (node (ref "R30") (pin "2") (pinfunction "2_2") (pintype "passive"))
      (node (ref "RT1") (pin "1") (pinfunction "1_1") (pintype "passive"))
      (node (ref "VCC1") (pin "1") (pinfunction "VCC_1") (pintype "passive"))
    )
    (net (code "32") (name "Battery_out") (class "Default")
      (node (ref "C22") (pin "1") (pinfunction "1_1") (pintype "passive"))
      (node (ref "C23") (pin "1") (pinfunction "1_1") (pintype "passive"))
      (node (ref "C9") (pin "2") (pintype "passive"))
      (node (ref "E2") (pin "1") (pinfunction "1_1") (pintype "passive"))
      (node (ref "PD3") (pin "1") (pinfunction "A_1") (pintype "passive"))
      (node (ref "PD7") (pin "1") (pinfunction "A_1") (pintype "passive"))
      (node (ref "PU4") (pin "1") (pinfunction "VIN_1") (pintype "passive"))
      (node (ref "Q2") (pin "2") (pinfunction "D_2") (pintype "passive"))
      (node (ref "R32") (pin "1") (pinfunction "1_1") (pintype "passive"))
      (node (ref "R38") (pin "2") (pinfunction "2_2") (pintype "passive"))
      (node (ref "RL1") (pin "1") (pinfunction "1_1") (pintype "passive"))
      (node (ref "RT1") (pin "2") (pinfunction "2_2") (pintype "passive"))
    )
    (net (code "33") (name "Boost_OUT") (class "Default")
      (node (ref "BOOST_PM1") (pin "4") (pinfunction "VIN_4") (pintype "passive"))
      (node (ref "R35") (pin "2") (pinfunction "2_2") (pintype "passive"))
      (node (ref "RT3") (pin "1") (pinfunction "1_1") (pintype "passive"))
    )
    (net (code "34") (name "GND") (class "Default")
      (node (ref "BOOST_PM1") (pin "2") (pinfunction "GND_2") (pintype "passive"))
      (node (ref "BOOST_PM1") (pin "3") (pinfunction "VING_3") (pintype "passive"))
      (node (ref "BOOST_PM1") (pin "5") (pinfunction "Hole_5") (pintype "passive"))
      (node (ref "BOOST_PM1") (pin "6") (pinfunction "Hole_6") (pintype "passive"))
      (node (ref "BOOST_PM1") (pin "7") (pinfunction "Hole_7") (pintype "passive"))
      (node (ref "BOOST_PM1") (pin "8") (pinfunction "Hole_8") (pintype "passive"))
      (node (ref "C1") (pin "2") (pinfunction "2_2") (pintype "passive"))
      (node (ref "C10") (pin "2") (pinfunction "2_2") (pintype "passive"))
      (node (ref "C11") (pin "2") (pinfunction "2_2") (pintype "passive"))
      (node (ref "C12") (pin "2") (pinfunction "2_2") (pintype "passive"))
      (node (ref "C13") (pin "1") (pinfunction "1_1") (pintype "passive"))
      (node (ref "C14") (pin "2") (pinfunction "2_2") (pintype "passive"))
      (node (ref "C15") (pin "2") (pinfunction "2_2") (pintype "passive"))
      (node (ref "C16") (pin "2") (pinfunction "2_2") (pintype "passive"))
      (node (ref "C17") (pin "1") (pinfunction "1_1") (pintype "passive"))
      (node (ref "C18") (pin "1") (pinfunction "1_1") (pintype "passive"))
      (node (ref "C19") (pin "1") (pinfunction "1_1") (pintype "passive"))
      (node (ref "C2") (pin "1") (pintype "passive"))
      (node (ref "C20") (pin "1") (pinfunction "1_1") (pintype "passive"))
      (node (ref "C21") (pin "2") (pinfunction "2_2") (pintype "passive"))
      (node (ref "C22") (pin "2") (pinfunction "2_2") (pintype "passive"))
      (node (ref "C23") (pin "2") (pinfunction "2_2") (pintype "passive"))
      (node (ref "C24") (pin "2") (pinfunction "2_2") (pintype "passive"))
      (node (ref "C25") (pin "2") (pinfunction "2_2") (pintype "passive"))
      (node (ref "C27") (pin "2") (pinfunction "2_2") (pintype "passive"))
      (node (ref "C28") (pin "2") (pinfunction "2_2") (pintype "passive"))
      (node (ref "C29") (pin "2") (pinfunction "2_2") (pintype "passive"))
      (node (ref "C3") (pin "2") (pinfunction "2_2") (pintype "passive"))
      (node (ref "C30") (pin "2") (pinfunction "2_2") (pintype "passive"))
      (node (ref "C31") (pin "2") (pinfunction "2_2") (pintype "passive"))
      (node (ref "C32") (pin "2") (pinfunction "2_2") (pintype "passive"))
      (node (ref "C4") (pin "2") (pinfunction "2_2") (pintype "passive"))
      (node (ref "C5") (pin "2") (pinfunction "2_2") (pintype "passive"))
      (node (ref "C6") (pin "2") (pinfunction "2_2") (pintype "passive"))
      (node (ref "C7") (pin "1") (pintype "passive"))
      (node (ref "C8") (pin "2") (pinfunction "2_2") (pintype "passive"))
      (node (ref "C9") (pin "1") (pintype "passive"))
      (node (ref "CR1") (pin "2") (pinfunction "2_2") (pintype "passive"))
      (node (ref "CU1") (pin "9") (pinfunction "VSS_9") (pintype "passive"))
      (node (ref "Cap1") (pin "2") (pinfunction "GND_2") (pintype "passive"))
      (node (ref "E1") (pin "2") (pinfunction "2_2") (pintype "passive"))
      (node (ref "E2") (pin "2") (pinfunction "2_2") (pintype "passive"))
      (node (ref "L2") (pin "2") (pinfunction "K_2") (pintype "passive"))
      (node (ref "L3") (pin "2") (pinfunction "K_2") (pintype "passive"))
      (node (ref "L4") (pin "2") (pinfunction "K_2") (pintype "passive"))
      (node (ref "L5") (pin "2") (pinfunction "K_2") (pintype "passive"))
      (node (ref "L6") (pin "2") (pinfunction "K_2") (pintype "passive"))
      (node (ref "LED1") (pin "2") (pinfunction "K_2") (pintype "passive"))
      (node (ref "M1") (pin "2") (pinfunction "GND_2") (pintype "passive"))
      (node (ref "OP1") (pin "3") (pinfunction "E_3") (pintype "passive"))
      (node (ref "PU1") (pin "1") (pintype "passive"))
      (node (ref "PU2") (pin "1") (pintype "passive"))
      (node (ref "PU3") (pin "2") (pinfunction "GND_2") (pintype "passive"))
      (node (ref "PU4") (pin "4") (pinfunction "CS_4") (pintype "passive"))
      (node (ref "PU4") (pin "5") (pinfunction "GND_5") (pintype "passive"))
      (node (ref "PU4") (pin "6") (pinfunction "GND_6") (pintype "passive"))
      (node (ref "PU4") (pin "7") (pinfunction "GND_7") (pintype "passive"))
      (node (ref "PU4") (pin "8") (pinfunction "GND_8") (pintype "passive"))
      (node (ref "Q3") (pin "3") (pinfunction "S_3") (pintype "passive"))
      (node (ref "R16") (pin "2") (pintype "passive"))
      (node (ref "R17") (pin "2") (pinfunction "2_2") (pintype "passive"))
      (node (ref "R2") (pin "1") (pinfunction "1_1") (pintype "passive"))
      (node (ref "R22") (pin "2") (pinfunction "2_2") (pintype "passive"))
      (node (ref "R23") (pin "2") (pinfunction "2_2") (pintype "passive"))
      (node (ref "R5") (pin "2") (pinfunction "2_2") (pintype "passive"))
      (node (ref "R8") (pin "2") (pinfunction "2_2") (pintype "passive"))
      (node (ref "S2") (pin "2") (pinfunction "2_2") (pintype "passive"))
      (node (ref "SS1") (pin "1") (pinfunction "A_1") (pintype "passive"))
      (node (ref "U1") (pin "2") (pinfunction "GND_2") (pintype "passive"))
      (node (ref "U2") (pin "2") (pinfunction "GXD_2") (pintype "passive"))
      (node (ref "U2") (pin "8") (pinfunction "Rs_8") (pintype "passive"))
      (node (ref "U3") (pin "23") (pinfunction "VSS_1_23") (pintype "passive"))
      (node (ref "U3") (pin "35") (pinfunction "VSS_2_35") (pintype "passive"))
      (node (ref "U3") (pin "47") (pinfunction "VSS_3_47") (pintype "passive"))
      (node (ref "U4") (pin "1") (pinfunction "A1_1") (pintype "passive"))
      (node (ref "U4") (pin "2") (pinfunction "A0_2") (pintype "passive"))
      (node (ref "U4") (pin "7") (pinfunction "GND_7") (pintype "passive"))
      (node (ref "U5") (pin "1") (pinfunction "A1_1") (pintype "passive"))
      (node (ref "U5") (pin "2") (pinfunction "A0_2") (pintype "passive"))
      (node (ref "U5") (pin "7") (pinfunction "GND_7") (pintype "passive"))
      (node (ref "U6") (pin "1") (pinfunction "A1_1") (pintype "passive"))
      (node (ref "U6") (pin "7") (pinfunction "GND_7") (pintype "passive"))
      (node (ref "VCC1") (pin "2") (pinfunction "GND_2") (pintype "passive"))
    )
    (net (code "35") (name "Moter") (class "Default")
      (node (ref "M1") (pin "1") (pinfunction "VCC_1") (pintype "passive"))
      (node (ref "PD3") (pin "2") (pinfunction "K_2") (pintype "passive"))
      (node (ref "PD4") (pin "2") (pinfunction "K_2") (pintype "passive"))
      (node (ref "PD7") (pin "2") (pinfunction "K_2") (pintype "passive"))
      (node (ref "PD8") (pin "2") (pinfunction "K_2") (pintype "passive"))
      (node (ref "R34") (pin "1") (pinfunction "1_1") (pintype "passive"))
    )
    (net (code "36") (name "Net-(BOOST_PM1-VOUT)") (class "Default")
      (node (ref "BOOST_PM1") (pin "1") (pinfunction "VOUT_1") (pintype "passive"))
      (node (ref "Q1") (pin "2") (pinfunction "D_2") (pintype "passive"))
    )
    (net (code "37") (name "Net-(C13-Pad2)") (class "Default")
      (node (ref "C13") (pin "2") (pinfunction "2_2") (pintype "passive"))
      (node (ref "C14") (pin "1") (pinfunction "1_1") (pintype "passive"))
      (node (ref "R3") (pin "2") (pinfunction "2_2") (pintype "passive"))
      (node (ref "R4") (pin "1") (pinfunction "1_1") (pintype "passive"))
    )
    (net (code "38") (name "Net-(CU1-HB)") (class "Default")
      (node (ref "C26") (pin "1") (pinfunction "1_1") (pintype "passive"))
      (node (ref "CU1") (pin "2") (pinfunction "HB_2") (pintype "passive"))
      (node (ref "D2") (pin "2") (pinfunction "2_2") (pintype "passive"))
    )
    (net (code "39") (name "Net-(CU1-HO)") (class "Default")
      (node (ref "CU1") (pin "3") (pinfunction "HO_3") (pintype "passive"))
      (node (ref "D3") (pin "2") (pinfunction "2_2") (pintype "passive"))
      (node (ref "R18") (pin "1") (pinfunction "1_1") (pintype "passive"))
    )
    (net (code "40") (name "Net-(CU1-HS)") (class "Default")
      (node (ref "C26") (pin "2") (pinfunction "2_2") (pintype "passive"))
      (node (ref "CU1") (pin "4") (pinfunction "HS_4") (pintype "passive"))
      (node (ref "L7") (pin "1") (pinfunction "1_1") (pintype "passive"))
      (node (ref "Q2") (pin "3") (pinfunction "S_3") (pintype "passive"))
      (node (ref "Q3") (pin "2") (pinfunction "D_2") (pintype "passive"))
      (node (ref "R19") (pin "2") (pinfunction "2_2") (pintype "passive"))
    )
    (net (code "41") (name "Net-(CU1-LO)") (class "Default")
      (node (ref "CU1") (pin "10") (pinfunction "LO_10") (pintype "passive"))
      (node (ref "D4") (pin "2") (pinfunction "K_2") (pintype "passive"))
      (node (ref "R21") (pin "1") (pinfunction "1_1") (pintype "passive"))
    )
    (net (code "42") (name "Net-(CU1-RDT)") (class "Default")
      (node (ref "CU1") (pin "6") (pinfunction "RDT_6") (pintype "passive"))
      (node (ref "R22") (pin "1") (pinfunction "1_1") (pintype "passive"))
    )
    (net (code "43") (name "Net-(D1-K)") (class "Default")
      (node (ref "C21") (pin "1") (pinfunction "1_1") (pintype "passive"))
      (node (ref "D1") (pin "2") (pinfunction "K_2") (pintype "passive"))
      (node (ref "U3") (pin "1") (pinfunction "VBAT_1") (pintype "passive"))
    )
    (net (code "44") (name "Net-(D4-A)") (class "Default")
      (node (ref "D4") (pin "1") (pinfunction "A_1") (pintype "passive"))
      (node (ref "Q3") (pin "1") (pinfunction "G_1") (pintype "passive"))
      (node (ref "R21") (pin "2") (pinfunction "2_2") (pintype "passive"))
      (node (ref "R23") (pin "1") (pinfunction "1_1") (pintype "passive"))
    )
    (net (code "45") (name "Net-(L2-A)") (class "Default")
      (node (ref "L2") (pin "1") (pinfunction "A_1") (pintype "passive"))
      (node (ref "R6") (pin "2") (pinfunction "2_2") (pintype "passive"))
    )
    (net (code "46") (name "Net-(L3-A)") (class "Default")
      (node (ref "L3") (pin "1") (pinfunction "A_1") (pintype "passive"))
      (node (ref "R7") (pin "1") (pinfunction "1_1") (pintype "passive"))
    )
    (net (code "47") (name "Net-(L4-A)") (class "Default")
      (node (ref "L4") (pin "1") (pinfunction "A_1") (pintype "passive"))
      (node (ref "R9") (pin "1") (pinfunction "1_1") (pintype "passive"))
    )
    (net (code "48") (name "Net-(L5-A)") (class "Default")
      (node (ref "L5") (pin "1") (pinfunction "A_1") (pintype "passive"))
      (node (ref "R10") (pin "1") (pinfunction "1_1") (pintype "passive"))
    )
    (net (code "49") (name "Net-(L6-A)") (class "Default")
      (node (ref "L6") (pin "1") (pinfunction "A_1") (pintype "passive"))
      (node (ref "R11") (pin "1") (pinfunction "1_1") (pintype "passive"))
    )
    (net (code "50") (name "Net-(LED1-A)") (class "Default")
      (node (ref "LED1") (pin "1") (pinfunction "A_1") (pintype "passive"))
      (node (ref "R20") (pin "1") (pinfunction "1_1") (pintype "passive"))
    )
    (net (code "51") (name "Net-(OP1-C)") (class "Default")
      (node (ref "OP1") (pin "4") (pinfunction "C_4") (pintype "passive"))
      (node (ref "Q1") (pin "1") (pinfunction "G_1") (pintype "passive"))
      (node (ref "RPL1") (pin "2") (pinfunction "2_2") (pintype "passive"))
    )
    (net (code "52") (name "Net-(OP1-K)") (class "Default")
      (node (ref "OP1") (pin "2") (pinfunction "K_2") (pintype "passive"))
      (node (ref "R17") (pin "1") (pinfunction "1_1") (pintype "passive"))
    )
    (net (code "53") (name "Net-(PU3-VIN)") (class "Default")
      (node (ref "C7") (pin "2") (pintype "passive"))
      (node (ref "PU3") (pin "3") (pinfunction "VIN_3") (pintype "passive"))
      (node (ref "RL1") (pin "2") (pinfunction "2_2") (pintype "passive"))
    )
    (net (code "54") (name "Net-(PU4-FB)") (class "Default")
      (node (ref "PU4") (pin "3") (pinfunction "FB_3") (pintype "passive"))
      (node (ref "R1") (pin "1") (pinfunction "1_1") (pintype "passive"))
      (node (ref "R2") (pin "2") (pinfunction "2_2") (pintype "passive"))
    )
    (net (code "55") (name "Net-(PU4-SW)") (class "Default")
      (node (ref "L1") (pin "1") (pinfunction "1_1") (pintype "passive"))
      (node (ref "PU4") (pin "2") (pinfunction "SW_2") (pintype "passive"))
      (node (ref "SS1") (pin "2") (pinfunction "K_2") (pintype "passive"))
    )
    (net (code "56") (name "Net-(Q2-G)") (class "Default")
      (node (ref "D3") (pin "1") (pinfunction "1_1") (pintype "passive"))
      (node (ref "Q2") (pin "1") (pinfunction "G_1") (pintype "passive"))
      (node (ref "R18") (pin "2") (pinfunction "2_2") (pintype "passive"))
      (node (ref "R19") (pin "1") (pinfunction "1_1") (pintype "passive"))
    )
    (net (code "57") (name "Net-(U3-BOOT0)") (class "Default")
      (node (ref "R16") (pin "1") (pintype "passive"))
      (node (ref "U3") (pin "44") (pinfunction "BOOT0_44") (pintype "passive"))
    )
    (net (code "58") (name "Net-(U3-NRST)") (class "Default")
      (node (ref "CR1") (pin "1") (pinfunction "1_1") (pintype "passive"))
      (node (ref "R14") (pin "2") (pintype "passive"))
      (node (ref "R15") (pin "2") (pintype "passive"))
      (node (ref "U3") (pin "7") (pinfunction "NRST_7") (pintype "passive"))
    )
    (net (code "59") (name "Net-(U3-PD0{slash}OSC_IN)") (class "Default")
      (node (ref "C20") (pin "2") (pinfunction "2_2") (pintype "passive"))
      (node (ref "U3") (pin "5") (pinfunction "PD0/OSC_IN_5") (pintype "passive"))
      (node (ref "Y1") (pin "2") (pinfunction "OSC2_2") (pintype "passive"))
    )
    (net (code "60") (name "Net-(U3-PDI{slash}OSC_OUT)") (class "Default")
      (node (ref "C19") (pin "2") (pinfunction "2_2") (pintype "passive"))
      (node (ref "U3") (pin "6") (pinfunction "PDI/OSC_OUT_6") (pintype "passive"))
      (node (ref "Y1") (pin "1") (pinfunction "OSC1_1") (pintype "passive"))
    )
    (net (code "61") (name "Net-(U4-IN+)") (class "Default")
      (node (ref "C33") (pin "1") (pinfunction "1_1") (pintype "passive"))
      (node (ref "R30") (pin "1") (pinfunction "1_1") (pintype "passive"))
      (node (ref "U4") (pin "10") (pinfunction "IN+_10") (pintype "passive"))
    )
    (net (code "62") (name "Net-(U4-IN-)") (class "Default")
      (node (ref "C33") (pin "2") (pinfunction "2_2") (pintype "passive"))
      (node (ref "R38") (pin "1") (pinfunction "1_1") (pintype "passive"))
      (node (ref "U4") (pin "9") (pinfunction "IN-_9") (pintype "passive"))
    )
    (net (code "63") (name "Net-(U5-IN+)") (class "Default")
      (node (ref "C34") (pin "1") (pinfunction "1_1") (pintype "passive"))
      (node (ref "R33") (pin "1") (pinfunction "1_1") (pintype "passive"))
      (node (ref "U5") (pin "10") (pinfunction "IN+_10") (pintype "passive"))
    )
    (net (code "64") (name "Net-(U5-IN-)") (class "Default")
      (node (ref "C34") (pin "2") (pinfunction "2_2") (pintype "passive"))
      (node (ref "R39") (pin "1") (pinfunction "1_1") (pintype "passive"))
      (node (ref "U5") (pin "9") (pinfunction "IN-_9") (pintype "passive"))
    )
    (net (code "65") (name "Net-(U6-A0)") (class "Default")
      (node (ref "R36") (pin "1") (pinfunction "1_1") (pintype "passive"))
      (node (ref "U6") (pin "2") (pinfunction "A0_2") (pintype "passive"))
    )
    (net (code "66") (name "Net-(U6-IN+)") (class "Default")
      (node (ref "C35") (pin "1") (pinfunction "1_1") (pintype "passive"))
      (node (ref "R35") (pin "1") (pinfunction "1_1") (pintype "passive"))
      (node (ref "U6") (pin "10") (pinfunction "IN+_10") (pintype "passive"))
    )
    (net (code "67") (name "Net-(U6-IN-)") (class "Default")
      (node (ref "C35") (pin "2") (pinfunction "2_2") (pintype "passive"))
      (node (ref "R40") (pin "1") (pinfunction "1_1") (pintype "passive"))
      (node (ref "U6") (pin "9") (pinfunction "IN-_9") (pintype "passive"))
    )
    (net (code "68") (name "Power_Cap") (class "Default")
      (node (ref "Cap1") (pin "1") (pinfunction "VCC_1") (pintype "passive"))
      (node (ref "Q1") (pin "3") (pinfunction "S_3") (pintype "passive"))
      (node (ref "R31") (pin "1") (pinfunction "1_1") (pintype "passive"))
      (node (ref "R39") (pin "2") (pinfunction "2_2") (pintype "passive"))
      (node (ref "RPL1") (pin "1") (pinfunction "1_1") (pintype "passive"))
      (node (ref "RT2") (pin "2") (pinfunction "2_2") (pintype "passive"))
    )
    (net (code "69") (name "Power_Charge") (class "Default")
      (node (ref "C27") (pin "1") (pinfunction "1_1") (pintype "passive"))
      (node (ref "C28") (pin "1") (pinfunction "1_1") (pintype "passive"))
      (node (ref "C29") (pin "1") (pinfunction "1_1") (pintype "passive"))
      (node (ref "L7") (pin "2") (pinfunction "2_2") (pintype "passive"))
      (node (ref "PD1") (pin "1") (pinfunction "A_1") (pintype "passive"))
      (node (ref "PD5") (pin "1") (pinfunction "A_1") (pintype "passive"))
      (node (ref "R20") (pin "2") (pinfunction "2_2") (pintype "passive"))
    )
    (net (code "70") (name "Power_Charge_out") (class "Default")
      (node (ref "PD1") (pin "2") (pinfunction "K_2") (pintype "passive"))
      (node (ref "PD5") (pin "2") (pinfunction "K_2") (pintype "passive"))
      (node (ref "R33") (pin "2") (pinfunction "2_2") (pintype "passive"))
      (node (ref "RT2") (pin "1") (pinfunction "1_1") (pintype "passive"))
    )
    (net (code "71") (name "SUPERCAP_OUT") (class "Default")
      (node (ref "PD4") (pin "1") (pinfunction "A_1") (pintype "passive"))
      (node (ref "PD8") (pin "1") (pinfunction "A_1") (pintype "passive"))
      (node (ref "R40") (pin "2") (pinfunction "2_2") (pintype "passive"))
      (node (ref "RT3") (pin "2") (pinfunction "2_2") (pintype "passive"))
    )
    (net (code "72") (name "VDDA") (class "Default")
      (node (ref "C15") (pin "1") (pinfunction "1_1") (pintype "passive"))
      (node (ref "C16") (pin "1") (pinfunction "1_1") (pintype "passive"))
      (node (ref "R4") (pin "2") (pinfunction "2_2") (pintype "passive"))
      (node (ref "U3") (pin "9") (pinfunction "VDDA_9") (pintype "passive"))
    )
    (net (code "73") (name "VSSA") (class "Default")
      (node (ref "R5") (pin "1") (pinfunction "1_1") (pintype "passive"))
      (node (ref "U3") (pin "8") (pinfunction "VSSA_8") (pintype "passive"))
    )
    (net (code "74") (name "unconnected-(CU1-NC-Pad5)") (class "Default")
      (node (ref "CU1") (pin "5") (pinfunction "NC_5") (pintype "passive"))
    )
    (net (code "75") (name "unconnected-(U2-Vref-Pad5)") (class "Default")
      (node (ref "U2") (pin "5") (pinfunction "Vref_5") (pintype "passive"))
    )
    (net (code "76") (name "unconnected-(U3-PA1{slash}USART2_RTS{slash}ADC12_0IN1{slash}TIM2_CH2-Pad11)") (class "Default")
      (node (ref "U3") (pin "11") (pinfunction "PA1/USART2_RTS/ADC12_0IN1/TIM2_CH2_11") (pintype "passive"))
    )
    (net (code "77") (name "unconnected-(U3-PA2{slash}USART2_TX{slash}ADC12_IN2{slash}TIM2_CH3-Pad12)") (class "Default")
      (node (ref "U3") (pin "12") (pinfunction "PA2/USART2_TX/ADC12_IN2/TIM2_CH3_12") (pintype "passive"))
    )
    (net (code "78") (name "unconnected-(U3-PA7{slash}SPI1_MOSI{slash}ADC12_IN7{slash}TIM3_CH2{slash}TIM1_CH1N-Pad17)") (class "Default")
      (node (ref "U3") (pin "17") (pinfunction "PA7/SPI1_MOSI/ADC12_IN7/TIM3_CH2/TIM1_CH1N_17") (pintype "passive"))
    )
    (net (code "79") (name "unconnected-(U3-PA8{slash}USART1_CK{slash}TIM1_CH1{slash}MCO-Pad29)") (class "Default")
      (node (ref "U3") (pin "29") (pinfunction "PA8/USART1_CK/TIM1_CH1/MCO_29") (pintype "passive"))
    )
    (net (code "80") (name "unconnected-(U3-PA9{slash}USART1_TX{slash}TIM1_CH2-Pad30)") (class "Default")
      (node (ref "U3") (pin "30") (pinfunction "PA9/USART1_TX/TIM1_CH2_30") (pintype "passive"))
    )
    (net (code "81") (name "unconnected-(U3-PA10{slash}USART1_RX{slash}TIM1_CH3-Pad31)") (class "Default")
      (node (ref "U3") (pin "31") (pinfunction "PA10/USART1_RX/TIM1_CH3_31") (pintype "passive"))
    )
    (net (code "82") (name "unconnected-(U3-PA11{slash}USART1_CTS{slash}CANRX{slash}USBDM{slash}TIM1_CH4-Pad32)") (class "Default")
      (node (ref "U3") (pin "32") (pinfunction "PA11/USART1_CTS/CANRX/USBDM/TIM1_CH4_32") (pintype "passive"))
    )
    (net (code "83") (name "unconnected-(U3-PA12{slash}USART1_RTS{slash}CANTX{slash}USBDP{slash}TIM1_ETR-Pad33)") (class "Default")
      (node (ref "U3") (pin "33") (pinfunction "PA12/USART1_RTS/CANTX/USBDP/TIM1_ETR_33") (pintype "passive"))
    )
    (net (code "84") (name "unconnected-(U3-PAO{slash}WKUP{slash}USART2_CTS{slash}ADC12_IN0{slash}TIM2_CH1_ETR-Pad10)") (class "Default")
      (node (ref "U3") (pin "10") (pinfunction "PAO/WKUP/USART2_CTS/ADC12_IN0/TIM2_CH1_ETR_10") (pintype "passive"))
    )
    (net (code "85") (name "unconnected-(U3-PB0{slash}ADC12_IN8{slash}TIM3_CH3{slash}TIM1_CH2N-Pad18)") (class "Default")
      (node (ref "U3") (pin "18") (pinfunction "PB0/ADC12_IN8/TIM3_CH3/TIM1_CH2N_18") (pintype "passive"))
    )
    (net (code "86") (name "unconnected-(U3-PB1{slash}ADC12_IN9{slash}TIM3_CH4{slash}TIM1_CH3N-Pad19)") (class "Default")
      (node (ref "U3") (pin "19") (pinfunction "PB1/ADC12_IN9/TIM3_CH4/TIM1_CH3N_19") (pintype "passive"))
    )
    (net (code "87") (name "unconnected-(U3-PB2{slash}BOOT1-Pad20)") (class "Default")
      (node (ref "U3") (pin "20") (pinfunction "PB2/BOOT1_20") (pintype "passive"))
    )
    (net (code "88") (name "unconnected-(U3-PB12{slash}SPI2_NSS{slash}I2C2_SMBAI{slash}USART3_CK{slash}TIM1_BKIN-Pad25)") (class "Default")
      (node (ref "U3") (pin "25") (pinfunction "PB12/SPI2_NSS/I2C2_SMBAI/USART3_CK/TIM1_BKIN_25") (pintype "passive"))
    )
    (net (code "89") (name "unconnected-(U3-PB13{slash}SPI2_SCK{slash}USART3_CTS{slash}TIM1_CH1N-Pad26)") (class "Default")
      (node (ref "U3") (pin "26") (pinfunction "PB13/SPI2_SCK/USART3_CTS/TIM1_CH1N_26") (pintype "passive"))
    )
    (net (code "90") (name "unconnected-(U3-PB14{slash}SPI2_MISO{slash}USART3_RTS{slash}TIM1_CH2N-Pad27)") (class "Default")
      (node (ref "U3") (pin "27") (pinfunction "PB14/SPI2_MISO/USART3_RTS/TIM1_CH2N_27") (pintype "passive"))
    )
    (net (code "91") (name "unconnected-(U3-PB15{slash}SPI2_MOSI{slash}TIM1_CH3N-Pad28)") (class "Default")
      (node (ref "U3") (pin "28") (pinfunction "PB15/SPI2_MOSI/TIM1_CH3N_28") (pintype "passive"))
    )
    (net (code "92") (name "unconnected-(U3-PC13{slash}TAMPER-RTC-Pad2)") (class "Default")
      (node (ref "U3") (pin "2") (pinfunction "PC13/TAMPER-RTC_2") (pintype "passive"))
    )
    (net (code "93") (name "unconnected-(U3-PC14{slash}OSC32_IN-Pad3)") (class "Default")
      (node (ref "U3") (pin "3") (pinfunction "PC14/OSC32_IN_3") (pintype "passive"))
    )
    (net (code "94") (name "unconnected-(U3-PC15{slash}OSC32_OUT-Pad4)") (class "Default")
      (node (ref "U3") (pin "4") (pinfunction "PC15/OSC32_OUT_4") (pintype "passive"))
    )
    (net (code "95") (name "unconnected-(U4-Alert-Pad3)") (class "Default")
      (node (ref "U4") (pin "3") (pinfunction "Alert_3") (pintype "passive"))
    )
    (net (code "96") (name "unconnected-(U5-Alert-Pad3)") (class "Default")
      (node (ref "U5") (pin "3") (pinfunction "Alert_3") (pintype "passive"))
    )
    (net (code "97") (name "unconnected-(U6-Alert-Pad3)") (class "Default")
      (node (ref "U6") (pin "3") (pinfunction "Alert_3") (pintype "passive"))
    )
  )
)
